# M2maleDouble_M2female.net
KiCad netlist of a schematic drawn in Altium Designer
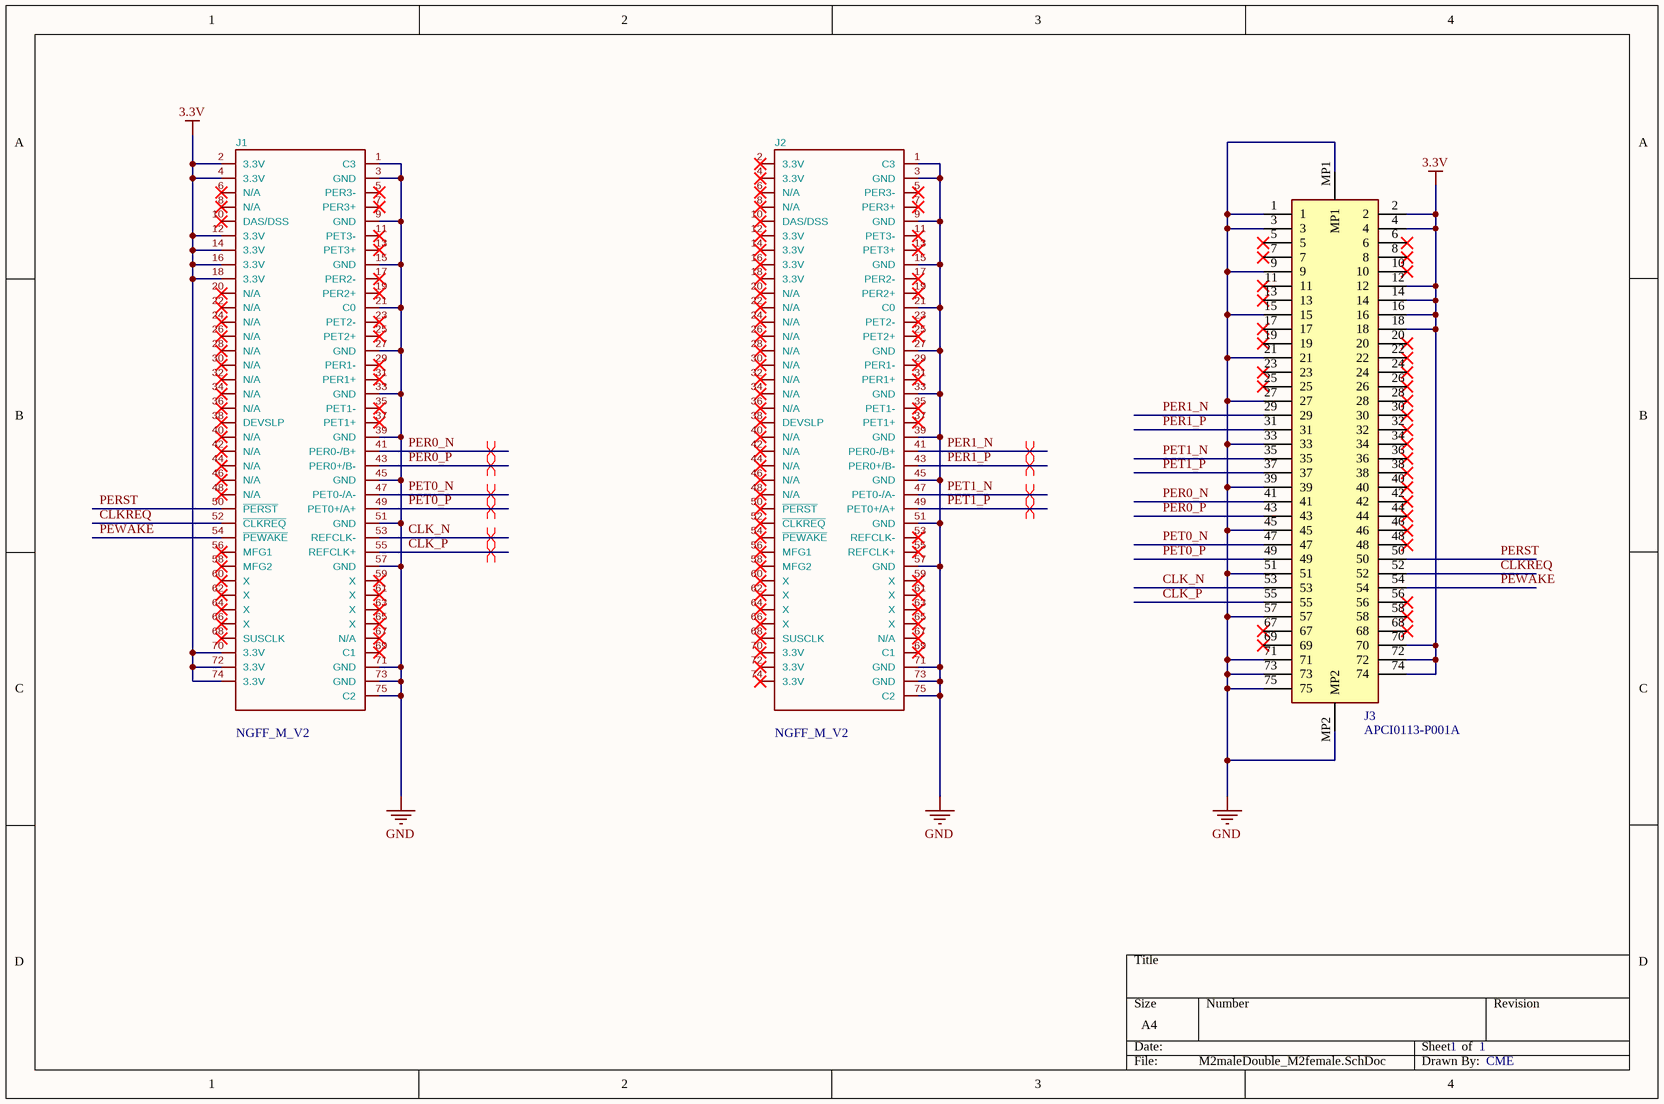
[diagram p0: M2maleDouble_M2female.SchDoc]

(export (version "E")
  (design (tool "Eeschema 10.0.6"))
  (components
    (comp (ref "J1")
      (value "NGFF_M_V2")
      (footprint "M2male_M2female_miniDP:M.2-M-KEY-2280-V2")
      (libsource (lib "M2male_M2female_miniDP") (part "NGFF_M_V2"))
    )
    (comp (ref "J2")
      (value "NGFF_M_V2")
      (footprint "M2male_M2female_miniDP:M.2-M-KEY-2280-V2")
      (libsource (lib "M2male_M2female_miniDP") (part "NGFF_M_V2"))
    )
    (comp (ref "J3")
      (value "APCI0113-P001A")
      (footprint "CME_LIB:APCI0113P001A")
      (description "Connector")
      (libsource (lib "CME_LIB") (part "APCI0113-P001A"))
    )
  )
  (nets
    (net (code "1") (name "/CLKREQ") (class "Default")
      (node (ref "J1") (pin "52") (pinfunction "~{CLKREQ}_52") (pintype "passive"))
      (node (ref "J3") (pin "52") (pinfunction "52_52") (pintype "passive"))
    )
    (net (code "2") (name "/CLK_N") (class "Default")
      (node (ref "J1") (pin "53") (pinfunction "REFCLK-_53") (pintype "passive"))
      (node (ref "J3") (pin "53") (pinfunction "53_53") (pintype "passive"))
    )
    (net (code "3") (name "/CLK_P") (class "Default")
      (node (ref "J1") (pin "55") (pinfunction "REFCLK+_55") (pintype "passive"))
      (node (ref "J3") (pin "55") (pinfunction "55_55") (pintype "passive"))
    )
    (net (code "4") (name "/PER0_N") (class "Default")
      (node (ref "J1") (pin "41") (pinfunction "PER0-/B+_41") (pintype "passive"))
      (node (ref "J3") (pin "41") (pinfunction "41_41") (pintype "passive"))
    )
    (net (code "5") (name "/PER0_P") (class "Default")
      (node (ref "J1") (pin "43") (pinfunction "PER0+/B-_43") (pintype "passive"))
      (node (ref "J3") (pin "43") (pinfunction "43_43") (pintype "passive"))
    )
    (net (code "6") (name "/PER1_N") (class "Default")
      (node (ref "J2") (pin "41") (pinfunction "PER0-/B+_41") (pintype "passive"))
      (node (ref "J3") (pin "29") (pinfunction "29_29") (pintype "passive"))
    )
    (net (code "7") (name "/PER1_P") (class "Default")
      (node (ref "J2") (pin "43") (pinfunction "PER0+/B-_43") (pintype "passive"))
      (node (ref "J3") (pin "31") (pinfunction "31_31") (pintype "passive"))
    )
    (net (code "8") (name "/PERST") (class "Default")
      (node (ref "J1") (pin "50") (pinfunction "~{PERST}_50") (pintype "passive"))
      (node (ref "J3") (pin "50") (pinfunction "50_50") (pintype "passive"))
    )
    (net (code "9") (name "/PET0_N") (class "Default")
      (node (ref "J1") (pin "47") (pinfunction "PET0-/A-_47") (pintype "passive"))
      (node (ref "J3") (pin "47") (pinfunction "47_47") (pintype "passive"))
    )
    (net (code "10") (name "/PET0_P") (class "Default")
      (node (ref "J1") (pin "49") (pinfunction "PET0+/A+_49") (pintype "passive"))
      (node (ref "J3") (pin "49") (pinfunction "49_49") (pintype "passive"))
    )
    (net (code "11") (name "/PET1_N") (class "Default")
      (node (ref "J2") (pin "47") (pinfunction "PET0-/A-_47") (pintype "passive"))
      (node (ref "J3") (pin "35") (pinfunction "35_35") (pintype "passive"))
    )
    (net (code "12") (name "/PET1_P") (class "Default")
      (node (ref "J2") (pin "49") (pinfunction "PET0+/A+_49") (pintype "passive"))
      (node (ref "J3") (pin "37") (pinfunction "37_37") (pintype "passive"))
    )
    (net (code "13") (name "/PEWAKE") (class "Default")
      (node (ref "J1") (pin "54") (pinfunction "~{PEWAKE}_54") (pintype "passive"))
      (node (ref "J3") (pin "54") (pinfunction "54_54") (pintype "passive"))
    )
    (net (code "14") (name "3.3V") (class "Default")
      (node (ref "J1") (pin "12") (pinfunction "3.3V_12") (pintype "passive"))
      (node (ref "J1") (pin "14") (pinfunction "3.3V_14") (pintype "passive"))
      (node (ref "J1") (pin "16") (pinfunction "3.3V_16") (pintype "passive"))
      (node (ref "J1") (pin "18") (pinfunction "3.3V_18") (pintype "passive"))
      (node (ref "J1") (pin "2") (pinfunction "3.3V_2") (pintype "passive"))
      (node (ref "J1") (pin "4") (pinfunction "3.3V_4") (pintype "passive"))
      (node (ref "J1") (pin "70") (pinfunction "3.3V_70") (pintype "passive"))
      (node (ref "J1") (pin "72") (pinfunction "3.3V_72") (pintype "passive"))
      (node (ref "J1") (pin "74") (pinfunction "3.3V_74") (pintype "passive"))
      (node (ref "J3") (pin "12") (pinfunction "12_12") (pintype "passive"))
      (node (ref "J3") (pin "14") (pinfunction "14_14") (pintype "passive"))
      (node (ref "J3") (pin "16") (pinfunction "16_16") (pintype "passive"))
      (node (ref "J3") (pin "18") (pinfunction "18_18") (pintype "passive"))
      (node (ref "J3") (pin "2") (pinfunction "2_2") (pintype "passive"))
      (node (ref "J3") (pin "4") (pinfunction "4_4") (pintype "passive"))
      (node (ref "J3") (pin "70") (pinfunction "70_70") (pintype "passive"))
      (node (ref "J3") (pin "72") (pinfunction "72_72") (pintype "passive"))
      (node (ref "J3") (pin "74") (pinfunction "74_74") (pintype "passive"))
    )
    (net (code "15") (name "GND") (class "Default")
      (node (ref "J1") (pin "1") (pinfunction "C3_1") (pintype "passive"))
      (node (ref "J1") (pin "15") (pinfunction "GND_15") (pintype "passive"))
      (node (ref "J1") (pin "21") (pinfunction "C0_21") (pintype "passive"))
      (node (ref "J1") (pin "27") (pinfunction "GND_27") (pintype "passive"))
      (node (ref "J1") (pin "3") (pinfunction "GND_3") (pintype "passive"))
      (node (ref "J1") (pin "33") (pinfunction "GND_33") (pintype "passive"))
      (node (ref "J1") (pin "39") (pinfunction "GND_39") (pintype "passive"))
      (node (ref "J1") (pin "45") (pinfunction "GND_45") (pintype "passive"))
      (node (ref "J1") (pin "51") (pinfunction "GND_51") (pintype "passive"))
      (node (ref "J1") (pin "57") (pinfunction "GND_57") (pintype "passive"))
      (node (ref "J1") (pin "71") (pinfunction "GND_71") (pintype "passive"))
      (node (ref "J1") (pin "73") (pinfunction "GND_73") (pintype "passive"))
      (node (ref "J1") (pin "75") (pinfunction "C2_75") (pintype "passive"))
      (node (ref "J1") (pin "9") (pinfunction "GND_9") (pintype "passive"))
      (node (ref "J2") (pin "1") (pinfunction "C3_1") (pintype "passive"))
      (node (ref "J2") (pin "15") (pinfunction "GND_15") (pintype "passive"))
      (node (ref "J2") (pin "21") (pinfunction "C0_21") (pintype "passive"))
      (node (ref "J2") (pin "27") (pinfunction "GND_27") (pintype "passive"))
      (node (ref "J2") (pin "3") (pinfunction "GND_3") (pintype "passive"))
      (node (ref "J2") (pin "33") (pinfunction "GND_33") (pintype "passive"))
      (node (ref "J2") (pin "39") (pinfunction "GND_39") (pintype "passive"))
      (node (ref "J2") (pin "45") (pinfunction "GND_45") (pintype "passive"))
      (node (ref "J2") (pin "51") (pinfunction "GND_51") (pintype "passive"))
      (node (ref "J2") (pin "57") (pinfunction "GND_57") (pintype "passive"))
      (node (ref "J2") (pin "71") (pinfunction "GND_71") (pintype "passive"))
      (node (ref "J2") (pin "73") (pinfunction "GND_73") (pintype "passive"))
      (node (ref "J2") (pin "75") (pinfunction "C2_75") (pintype "passive"))
      (node (ref "J2") (pin "9") (pinfunction "GND_9") (pintype "passive"))
      (node (ref "J3") (pin "1") (pinfunction "1_1") (pintype "passive"))
      (node (ref "J3") (pin "15") (pinfunction "15_15") (pintype "passive"))
      (node (ref "J3") (pin "21") (pinfunction "21_21") (pintype "passive"))
      (node (ref "J3") (pin "27") (pinfunction "27_27") (pintype "passive"))
      (node (ref "J3") (pin "3") (pinfunction "3_3") (pintype "passive"))
      (node (ref "J3") (pin "33") (pinfunction "33_33") (pintype "passive"))
      (node (ref "J3") (pin "39") (pinfunction "39_39") (pintype "passive"))
      (node (ref "J3") (pin "45") (pinfunction "45_45") (pintype "passive"))
      (node (ref "J3") (pin "51") (pinfunction "51_51") (pintype "passive"))
      (node (ref "J3") (pin "57") (pinfunction "57_57") (pintype "passive"))
      (node (ref "J3") (pin "71") (pinfunction "71_71") (pintype "passive"))
      (node (ref "J3") (pin "73") (pinfunction "73_73") (pintype "passive"))
      (node (ref "J3") (pin "75") (pinfunction "75_75") (pintype "passive"))
      (node (ref "J3") (pin "9") (pinfunction "9_9") (pintype "passive"))
      (node (ref "J3") (pin "MP1") (pinfunction "MP1_MP1") (pintype "passive"))
      (node (ref "J3") (pin "MP2") (pinfunction "MP2_MP2") (pintype "passive"))
    )
    (net (code "16") (name "unconnected-(J1-C1-Pad69)") (class "Default")
      (node (ref "J1") (pin "69") (pinfunction "C1_69") (pintype "passive+no_connect"))
    )
    (net (code "17") (name "unconnected-(J1-DAS{slash}DSS-Pad10)") (class "Default")
      (node (ref "J1") (pin "10") (pinfunction "DAS/DSS_10") (pintype "passive+no_connect"))
    )
    (net (code "18") (name "unconnected-(J1-DEVSLP-Pad38)") (class "Default")
      (node (ref "J1") (pin "38") (pinfunction "DEVSLP_38") (pintype "passive+no_connect"))
    )
    (net (code "19") (name "unconnected-(J1-MFG1-Pad56)") (class "Default")
      (node (ref "J1") (pin "56") (pinfunction "MFG1_56") (pintype "passive+no_connect"))
    )
    (net (code "20") (name "unconnected-(J1-MFG2-Pad58)") (class "Default")
      (node (ref "J1") (pin "58") (pinfunction "MFG2_58") (pintype "passive+no_connect"))
    )
    (net (code "21") (name "unconnected-(J1-N{slash}A-Pad6)") (class "Default")
      (node (ref "J1") (pin "6") (pinfunction "N/A_6") (pintype "passive+no_connect"))
    )
    (net (code "22") (name "unconnected-(J1-N{slash}A-Pad8)") (class "Default")
      (node (ref "J1") (pin "8") (pinfunction "N/A_8") (pintype "passive+no_connect"))
    )
    (net (code "23") (name "unconnected-(J1-N{slash}A-Pad20)") (class "Default")
      (node (ref "J1") (pin "20") (pinfunction "N/A_20") (pintype "passive+no_connect"))
    )
    (net (code "24") (name "unconnected-(J1-N{slash}A-Pad22)") (class "Default")
      (node (ref "J1") (pin "22") (pinfunction "N/A_22") (pintype "passive+no_connect"))
    )
    (net (code "25") (name "unconnected-(J1-N{slash}A-Pad24)") (class "Default")
      (node (ref "J1") (pin "24") (pinfunction "N/A_24") (pintype "passive+no_connect"))
    )
    (net (code "26") (name "unconnected-(J1-N{slash}A-Pad26)") (class "Default")
      (node (ref "J1") (pin "26") (pinfunction "N/A_26") (pintype "passive+no_connect"))
    )
    (net (code "27") (name "unconnected-(J1-N{slash}A-Pad28)") (class "Default")
      (node (ref "J1") (pin "28") (pinfunction "N/A_28") (pintype "passive+no_connect"))
    )
    (net (code "28") (name "unconnected-(J1-N{slash}A-Pad30)") (class "Default")
      (node (ref "J1") (pin "30") (pinfunction "N/A_30") (pintype "passive+no_connect"))
    )
    (net (code "29") (name "unconnected-(J1-N{slash}A-Pad32)") (class "Default")
      (node (ref "J1") (pin "32") (pinfunction "N/A_32") (pintype "passive+no_connect"))
    )
    (net (code "30") (name "unconnected-(J1-N{slash}A-Pad34)") (class "Default")
      (node (ref "J1") (pin "34") (pinfunction "N/A_34") (pintype "passive+no_connect"))
    )
    (net (code "31") (name "unconnected-(J1-N{slash}A-Pad36)") (class "Default")
      (node (ref "J1") (pin "36") (pinfunction "N/A_36") (pintype "passive+no_connect"))
    )
    (net (code "32") (name "unconnected-(J1-N{slash}A-Pad40)") (class "Default")
      (node (ref "J1") (pin "40") (pinfunction "N/A_40") (pintype "passive+no_connect"))
    )
    (net (code "33") (name "unconnected-(J1-N{slash}A-Pad42)") (class "Default")
      (node (ref "J1") (pin "42") (pinfunction "N/A_42") (pintype "passive+no_connect"))
    )
    (net (code "34") (name "unconnected-(J1-N{slash}A-Pad44)") (class "Default")
      (node (ref "J1") (pin "44") (pinfunction "N/A_44") (pintype "passive+no_connect"))
    )
    (net (code "35") (name "unconnected-(J1-N{slash}A-Pad46)") (class "Default")
      (node (ref "J1") (pin "46") (pinfunction "N/A_46") (pintype "passive+no_connect"))
    )
    (net (code "36") (name "unconnected-(J1-N{slash}A-Pad48)") (class "Default")
      (node (ref "J1") (pin "48") (pinfunction "N/A_48") (pintype "passive+no_connect"))
    )
    (net (code "37") (name "unconnected-(J1-N{slash}A-Pad67)") (class "Default")
      (node (ref "J1") (pin "67") (pinfunction "N/A_67") (pintype "passive+no_connect"))
    )
    (net (code "38") (name "unconnected-(J1-PER1+-Pad31)") (class "Default")
      (node (ref "J1") (pin "31") (pinfunction "PER1+_31") (pintype "passive+no_connect"))
    )
    (net (code "39") (name "unconnected-(J1-PER1--Pad29)") (class "Default")
      (node (ref "J1") (pin "29") (pinfunction "PER1-_29") (pintype "passive+no_connect"))
    )
    (net (code "40") (name "unconnected-(J1-PER2+-Pad19)") (class "Default")
      (node (ref "J1") (pin "19") (pinfunction "PER2+_19") (pintype "passive+no_connect"))
    )
    (net (code "41") (name "unconnected-(J1-PER2--Pad17)") (class "Default")
      (node (ref "J1") (pin "17") (pinfunction "PER2-_17") (pintype "passive+no_connect"))
    )
    (net (code "42") (name "unconnected-(J1-PER3+-Pad7)") (class "Default")
      (node (ref "J1") (pin "7") (pinfunction "PER3+_7") (pintype "passive+no_connect"))
    )
    (net (code "43") (name "unconnected-(J1-PER3--Pad5)") (class "Default")
      (node (ref "J1") (pin "5") (pinfunction "PER3-_5") (pintype "passive+no_connect"))
    )
    (net (code "44") (name "unconnected-(J1-PET1+-Pad37)") (class "Default")
      (node (ref "J1") (pin "37") (pinfunction "PET1+_37") (pintype "passive+no_connect"))
    )
    (net (code "45") (name "unconnected-(J1-PET1--Pad35)") (class "Default")
      (node (ref "J1") (pin "35") (pinfunction "PET1-_35") (pintype "passive+no_connect"))
    )
    (net (code "46") (name "unconnected-(J1-PET2+-Pad25)") (class "Default")
      (node (ref "J1") (pin "25") (pinfunction "PET2+_25") (pintype "passive+no_connect"))
    )
    (net (code "47") (name "unconnected-(J1-PET2--Pad23)") (class "Default")
      (node (ref "J1") (pin "23") (pinfunction "PET2-_23") (pintype "passive+no_connect"))
    )
    (net (code "48") (name "unconnected-(J1-PET3+-Pad13)") (class "Default")
      (node (ref "J1") (pin "13") (pinfunction "PET3+_13") (pintype "passive+no_connect"))
    )
    (net (code "49") (name "unconnected-(J1-PET3--Pad11)") (class "Default")
      (node (ref "J1") (pin "11") (pinfunction "PET3-_11") (pintype "passive+no_connect"))
    )
    (net (code "50") (name "unconnected-(J1-SUSCLK-Pad68)") (class "Default")
      (node (ref "J1") (pin "68") (pinfunction "SUSCLK_68") (pintype "passive+no_connect"))
    )
    (net (code "51") (name "unconnected-(J1-X-Pad59)") (class "Default")
      (node (ref "J1") (pin "59") (pinfunction "X_59") (pintype "passive+no_connect"))
    )
    (net (code "52") (name "unconnected-(J1-X-Pad60)") (class "Default")
      (node (ref "J1") (pin "60") (pinfunction "X_60") (pintype "passive+no_connect"))
    )
    (net (code "53") (name "unconnected-(J1-X-Pad61)") (class "Default")
      (node (ref "J1") (pin "61") (pinfunction "X_61") (pintype "passive+no_connect"))
    )
    (net (code "54") (name "unconnected-(J1-X-Pad62)") (class "Default")
      (node (ref "J1") (pin "62") (pinfunction "X_62") (pintype "passive+no_connect"))
    )
    (net (code "55") (name "unconnected-(J1-X-Pad63)") (class "Default")
      (node (ref "J1") (pin "63") (pinfunction "X_63") (pintype "passive+no_connect"))
    )
    (net (code "56") (name "unconnected-(J1-X-Pad64)") (class "Default")
      (node (ref "J1") (pin "64") (pinfunction "X_64") (pintype "passive+no_connect"))
    )
    (net (code "57") (name "unconnected-(J1-X-Pad65)") (class "Default")
      (node (ref "J1") (pin "65") (pinfunction "X_65") (pintype "passive+no_connect"))
    )
    (net (code "58") (name "unconnected-(J1-X-Pad66)") (class "Default")
      (node (ref "J1") (pin "66") (pinfunction "X_66") (pintype "passive+no_connect"))
    )
    (net (code "59") (name "unconnected-(J2-3.3V-Pad2)") (class "Default")
      (node (ref "J2") (pin "2") (pinfunction "3.3V_2") (pintype "passive+no_connect"))
    )
    (net (code "60") (name "unconnected-(J2-3.3V-Pad4)") (class "Default")
      (node (ref "J2") (pin "4") (pinfunction "3.3V_4") (pintype "passive+no_connect"))
    )
    (net (code "61") (name "unconnected-(J2-3.3V-Pad12)") (class "Default")
      (node (ref "J2") (pin "12") (pinfunction "3.3V_12") (pintype "passive+no_connect"))
    )
    (net (code "62") (name "unconnected-(J2-3.3V-Pad14)") (class "Default")
      (node (ref "J2") (pin "14") (pinfunction "3.3V_14") (pintype "passive+no_connect"))
    )
    (net (code "63") (name "unconnected-(J2-3.3V-Pad16)") (class "Default")
      (node (ref "J2") (pin "16") (pinfunction "3.3V_16") (pintype "passive+no_connect"))
    )
    (net (code "64") (name "unconnected-(J2-3.3V-Pad18)") (class "Default")
      (node (ref "J2") (pin "18") (pinfunction "3.3V_18") (pintype "passive+no_connect"))
    )
    (net (code "65") (name "unconnected-(J2-3.3V-Pad70)") (class "Default")
      (node (ref "J2") (pin "70") (pinfunction "3.3V_70") (pintype "passive+no_connect"))
    )
    (net (code "66") (name "unconnected-(J2-3.3V-Pad72)") (class "Default")
      (node (ref "J2") (pin "72") (pinfunction "3.3V_72") (pintype "passive+no_connect"))
    )
    (net (code "67") (name "unconnected-(J2-3.3V-Pad74)") (class "Default")
      (node (ref "J2") (pin "74") (pinfunction "3.3V_74") (pintype "passive+no_connect"))
    )
    (net (code "68") (name "unconnected-(J2-C1-Pad69)") (class "Default")
      (node (ref "J2") (pin "69") (pinfunction "C1_69") (pintype "passive+no_connect"))
    )
    (net (code "69") (name "unconnected-(J2-DAS{slash}DSS-Pad10)") (class "Default")
      (node (ref "J2") (pin "10") (pinfunction "DAS/DSS_10") (pintype "passive+no_connect"))
    )
    (net (code "70") (name "unconnected-(J2-DEVSLP-Pad38)") (class "Default")
      (node (ref "J2") (pin "38") (pinfunction "DEVSLP_38") (pintype "passive+no_connect"))
    )
    (net (code "71") (name "unconnected-(J2-MFG1-Pad56)") (class "Default")
      (node (ref "J2") (pin "56") (pinfunction "MFG1_56") (pintype "passive+no_connect"))
    )
    (net (code "72") (name "unconnected-(J2-MFG2-Pad58)") (class "Default")
      (node (ref "J2") (pin "58") (pinfunction "MFG2_58") (pintype "passive+no_connect"))
    )
    (net (code "73") (name "unconnected-(J2-N{slash}A-Pad6)") (class "Default")
      (node (ref "J2") (pin "6") (pinfunction "N/A_6") (pintype "passive+no_connect"))
    )
    (net (code "74") (name "unconnected-(J2-N{slash}A-Pad8)") (class "Default")
      (node (ref "J2") (pin "8") (pinfunction "N/A_8") (pintype "passive+no_connect"))
    )
    (net (code "75") (name "unconnected-(J2-N{slash}A-Pad20)") (class "Default")
      (node (ref "J2") (pin "20") (pinfunction "N/A_20") (pintype "passive+no_connect"))
    )
    (net (code "76") (name "unconnected-(J2-N{slash}A-Pad22)") (class "Default")
      (node (ref "J2") (pin "22") (pinfunction "N/A_22") (pintype "passive+no_connect"))
    )
    (net (code "77") (name "unconnected-(J2-N{slash}A-Pad24)") (class "Default")
      (node (ref "J2") (pin "24") (pinfunction "N/A_24") (pintype "passive+no_connect"))
    )
    (net (code "78") (name "unconnected-(J2-N{slash}A-Pad26)") (class "Default")
      (node (ref "J2") (pin "26") (pinfunction "N/A_26") (pintype "passive+no_connect"))
    )
    (net (code "79") (name "unconnected-(J2-N{slash}A-Pad28)") (class "Default")
      (node (ref "J2") (pin "28") (pinfunction "N/A_28") (pintype "passive+no_connect"))
    )
    (net (code "80") (name "unconnected-(J2-N{slash}A-Pad30)") (class "Default")
      (node (ref "J2") (pin "30") (pinfunction "N/A_30") (pintype "passive+no_connect"))
    )
    (net (code "81") (name "unconnected-(J2-N{slash}A-Pad32)") (class "Default")
      (node (ref "J2") (pin "32") (pinfunction "N/A_32") (pintype "passive+no_connect"))
    )
    (net (code "82") (name "unconnected-(J2-N{slash}A-Pad34)") (class "Default")
      (node (ref "J2") (pin "34") (pinfunction "N/A_34") (pintype "passive+no_connect"))
    )
    (net (code "83") (name "unconnected-(J2-N{slash}A-Pad36)") (class "Default")
      (node (ref "J2") (pin "36") (pinfunction "N/A_36") (pintype "passive+no_connect"))
    )
    (net (code "84") (name "unconnected-(J2-N{slash}A-Pad40)") (class "Default")
      (node (ref "J2") (pin "40") (pinfunction "N/A_40") (pintype "passive+no_connect"))
    )
    (net (code "85") (name "unconnected-(J2-N{slash}A-Pad42)") (class "Default")
      (node (ref "J2") (pin "42") (pinfunction "N/A_42") (pintype "passive+no_connect"))
    )
    (net (code "86") (name "unconnected-(J2-N{slash}A-Pad44)") (class "Default")
      (node (ref "J2") (pin "44") (pinfunction "N/A_44") (pintype "passive+no_connect"))
    )
    (net (code "87") (name "unconnected-(J2-N{slash}A-Pad46)") (class "Default")
      (node (ref "J2") (pin "46") (pinfunction "N/A_46") (pintype "passive+no_connect"))
    )
    (net (code "88") (name "unconnected-(J2-N{slash}A-Pad48)") (class "Default")
      (node (ref "J2") (pin "48") (pinfunction "N/A_48") (pintype "passive+no_connect"))
    )
    (net (code "89") (name "unconnected-(J2-N{slash}A-Pad67)") (class "Default")
      (node (ref "J2") (pin "67") (pinfunction "N/A_67") (pintype "passive+no_connect"))
    )
    (net (code "90") (name "unconnected-(J2-PER1+-Pad31)") (class "Default")
      (node (ref "J2") (pin "31") (pinfunction "PER1+_31") (pintype "passive+no_connect"))
    )
    (net (code "91") (name "unconnected-(J2-PER1--Pad29)") (class "Default")
      (node (ref "J2") (pin "29") (pinfunction "PER1-_29") (pintype "passive+no_connect"))
    )
    (net (code "92") (name "unconnected-(J2-PER2+-Pad19)") (class "Default")
      (node (ref "J2") (pin "19") (pinfunction "PER2+_19") (pintype "passive+no_connect"))
    )
    (net (code "93") (name "unconnected-(J2-PER2--Pad17)") (class "Default")
      (node (ref "J2") (pin "17") (pinfunction "PER2-_17") (pintype "passive+no_connect"))
    )
    (net (code "94") (name "unconnected-(J2-PER3+-Pad7)") (class "Default")
      (node (ref "J2") (pin "7") (pinfunction "PER3+_7") (pintype "passive+no_connect"))
    )
    (net (code "95") (name "unconnected-(J2-PER3--Pad5)") (class "Default")
      (node (ref "J2") (pin "5") (pinfunction "PER3-_5") (pintype "passive+no_connect"))
    )
    (net (code "96") (name "unconnected-(J2-PET1+-Pad37)") (class "Default")
      (node (ref "J2") (pin "37") (pinfunction "PET1+_37") (pintype "passive+no_connect"))
    )
    (net (code "97") (name "unconnected-(J2-PET1--Pad35)") (class "Default")
      (node (ref "J2") (pin "35") (pinfunction "PET1-_35") (pintype "passive+no_connect"))
    )
    (net (code "98") (name "unconnected-(J2-PET2+-Pad25)") (class "Default")
      (node (ref "J2") (pin "25") (pinfunction "PET2+_25") (pintype "passive+no_connect"))
    )
    (net (code "99") (name "unconnected-(J2-PET2--Pad23)") (class "Default")
      (node (ref "J2") (pin "23") (pinfunction "PET2-_23") (pintype "passive+no_connect"))
    )
    (net (code "100") (name "unconnected-(J2-PET3+-Pad13)") (class "Default")
      (node (ref "J2") (pin "13") (pinfunction "PET3+_13") (pintype "passive+no_connect"))
    )
    (net (code "101") (name "unconnected-(J2-PET3--Pad11)") (class "Default")
      (node (ref "J2") (pin "11") (pinfunction "PET3-_11") (pintype "passive+no_connect"))
    )
    (net (code "102") (name "unconnected-(J2-REFCLK+-Pad55)") (class "Default")
      (node (ref "J2") (pin "55") (pinfunction "REFCLK+_55") (pintype "passive+no_connect"))
    )
    (net (code "103") (name "unconnected-(J2-REFCLK--Pad53)") (class "Default")
      (node (ref "J2") (pin "53") (pinfunction "REFCLK-_53") (pintype "passive+no_connect"))
    )
    (net (code "104") (name "unconnected-(J2-SUSCLK-Pad68)") (class "Default")
      (node (ref "J2") (pin "68") (pinfunction "SUSCLK_68") (pintype "passive+no_connect"))
    )
    (net (code "105") (name "unconnected-(J2-X-Pad59)") (class "Default")
      (node (ref "J2") (pin "59") (pinfunction "X_59") (pintype "passive+no_connect"))
    )
    (net (code "106") (name "unconnected-(J2-X-Pad60)") (class "Default")
      (node (ref "J2") (pin "60") (pinfunction "X_60") (pintype "passive+no_connect"))
    )
    (net (code "107") (name "unconnected-(J2-X-Pad61)") (class "Default")
      (node (ref "J2") (pin "61") (pinfunction "X_61") (pintype "passive+no_connect"))
    )
    (net (code "108") (name "unconnected-(J2-X-Pad62)") (class "Default")
      (node (ref "J2") (pin "62") (pinfunction "X_62") (pintype "passive+no_connect"))
    )
    (net (code "109") (name "unconnected-(J2-X-Pad63)") (class "Default")
      (node (ref "J2") (pin "63") (pinfunction "X_63") (pintype "passive+no_connect"))
    )
    (net (code "110") (name "unconnected-(J2-X-Pad64)") (class "Default")
      (node (ref "J2") (pin "64") (pinfunction "X_64") (pintype "passive+no_connect"))
    )
    (net (code "111") (name "unconnected-(J2-X-Pad65)") (class "Default")
      (node (ref "J2") (pin "65") (pinfunction "X_65") (pintype "passive+no_connect"))
    )
    (net (code "112") (name "unconnected-(J2-X-Pad66)") (class "Default")
      (node (ref "J2") (pin "66") (pinfunction "X_66") (pintype "passive+no_connect"))
    )
    (net (code "113") (name "unconnected-(J2-~{CLKREQ}-Pad52)") (class "Default")
      (node (ref "J2") (pin "52") (pinfunction "~{CLKREQ}_52") (pintype "passive+no_connect"))
    )
    (net (code "114") (name "unconnected-(J2-~{PERST}-Pad50)") (class "Default")
      (node (ref "J2") (pin "50") (pinfunction "~{PERST}_50") (pintype "passive+no_connect"))
    )
    (net (code "115") (name "unconnected-(J2-~{PEWAKE}-Pad54)") (class "Default")
      (node (ref "J2") (pin "54") (pinfunction "~{PEWAKE}_54") (pintype "passive+no_connect"))
    )
    (net (code "116") (name "unconnected-(J3-Pad5)") (class "Default")
      (node (ref "J3") (pin "5") (pinfunction "5_5") (pintype "passive+no_connect"))
    )
    (net (code "117") (name "unconnected-(J3-Pad6)") (class "Default")
      (node (ref "J3") (pin "6") (pinfunction "6_6") (pintype "passive+no_connect"))
    )
    (net (code "118") (name "unconnected-(J3-Pad7)") (class "Default")
      (node (ref "J3") (pin "7") (pinfunction "7_7") (pintype "passive+no_connect"))
    )
    (net (code "119") (name "unconnected-(J3-Pad8)") (class "Default")
      (node (ref "J3") (pin "8") (pinfunction "8_8") (pintype "passive+no_connect"))
    )
    (net (code "120") (name "unconnected-(J3-Pad10)") (class "Default")
      (node (ref "J3") (pin "10") (pinfunction "10_10") (pintype "passive+no_connect"))
    )
    (net (code "121") (name "unconnected-(J3-Pad11)") (class "Default")
      (node (ref "J3") (pin "11") (pinfunction "11_11") (pintype "passive+no_connect"))
    )
    (net (code "122") (name "unconnected-(J3-Pad13)") (class "Default")
      (node (ref "J3") (pin "13") (pinfunction "13_13") (pintype "passive+no_connect"))
    )
    (net (code "123") (name "unconnected-(J3-Pad17)") (class "Default")
      (node (ref "J3") (pin "17") (pinfunction "17_17") (pintype "passive+no_connect"))
    )
    (net (code "124") (name "unconnected-(J3-Pad19)") (class "Default")
      (node (ref "J3") (pin "19") (pinfunction "19_19") (pintype "passive+no_connect"))
    )
    (net (code "125") (name "unconnected-(J3-Pad20)") (class "Default")
      (node (ref "J3") (pin "20") (pinfunction "20_20") (pintype "passive+no_connect"))
    )
    (net (code "126") (name "unconnected-(J3-Pad22)") (class "Default")
      (node (ref "J3") (pin "22") (pinfunction "22_22") (pintype "passive+no_connect"))
    )
    (net (code "127") (name "unconnected-(J3-Pad23)") (class "Default")
      (node (ref "J3") (pin "23") (pinfunction "23_23") (pintype "passive+no_connect"))
    )
    (net (code "128") (name "unconnected-(J3-Pad24)") (class "Default")
      (node (ref "J3") (pin "24") (pinfunction "24_24") (pintype "passive+no_connect"))
    )
    (net (code "129") (name "unconnected-(J3-Pad25)") (class "Default")
      (node (ref "J3") (pin "25") (pinfunction "25_25") (pintype "passive+no_connect"))
    )
    (net (code "130") (name "unconnected-(J3-Pad26)") (class "Default")
      (node (ref "J3") (pin "26") (pinfunction "26_26") (pintype "passive+no_connect"))
    )
    (net (code "131") (name "unconnected-(J3-Pad28)") (class "Default")
      (node (ref "J3") (pin "28") (pinfunction "28_28") (pintype "passive+no_connect"))
    )
    (net (code "132") (name "unconnected-(J3-Pad30)") (class "Default")
      (node (ref "J3") (pin "30") (pinfunction "30_30") (pintype "passive+no_connect"))
    )
    (net (code "133") (name "unconnected-(J3-Pad32)") (class "Default")
      (node (ref "J3") (pin "32") (pinfunction "32_32") (pintype "passive+no_connect"))
    )
    (net (code "134") (name "unconnected-(J3-Pad34)") (class "Default")
      (node (ref "J3") (pin "34") (pinfunction "34_34") (pintype "passive+no_connect"))
    )
    (net (code "135") (name "unconnected-(J3-Pad36)") (class "Default")
      (node (ref "J3") (pin "36") (pinfunction "36_36") (pintype "passive+no_connect"))
    )
    (net (code "136") (name "unconnected-(J3-Pad38)") (class "Default")
      (node (ref "J3") (pin "38") (pinfunction "38_38") (pintype "passive+no_connect"))
    )
    (net (code "137") (name "unconnected-(J3-Pad40)") (class "Default")
      (node (ref "J3") (pin "40") (pinfunction "40_40") (pintype "passive+no_connect"))
    )
    (net (code "138") (name "unconnected-(J3-Pad42)") (class "Default")
      (node (ref "J3") (pin "42") (pinfunction "42_42") (pintype "passive+no_connect"))
    )
    (net (code "139") (name "unconnected-(J3-Pad44)") (class "Default")
      (node (ref "J3") (pin "44") (pinfunction "44_44") (pintype "passive+no_connect"))
    )
    (net (code "140") (name "unconnected-(J3-Pad46)") (class "Default")
      (node (ref "J3") (pin "46") (pinfunction "46_46") (pintype "passive+no_connect"))
    )
    (net (code "141") (name "unconnected-(J3-Pad48)") (class "Default")
      (node (ref "J3") (pin "48") (pinfunction "48_48") (pintype "passive+no_connect"))
    )
    (net (code "142") (name "unconnected-(J3-Pad56)") (class "Default")
      (node (ref "J3") (pin "56") (pinfunction "56_56") (pintype "passive+no_connect"))
    )
    (net (code "143") (name "unconnected-(J3-Pad58)") (class "Default")
      (node (ref "J3") (pin "58") (pinfunction "58_58") (pintype "passive+no_connect"))
    )
    (net (code "144") (name "unconnected-(J3-Pad67)") (class "Default")
      (node (ref "J3") (pin "67") (pinfunction "67_67") (pintype "passive+no_connect"))
    )
    (net (code "145") (name "unconnected-(J3-Pad68)") (class "Default")
      (node (ref "J3") (pin "68") (pinfunction "68_68") (pintype "passive+no_connect"))
    )
    (net (code "146") (name "unconnected-(J3-Pad69)") (class "Default")
      (node (ref "J3") (pin "69") (pinfunction "69_69") (pintype "passive+no_connect"))
    )
  )
)
